# snoozerly.net
KiCad netlist of a schematic drawn in EAGLE
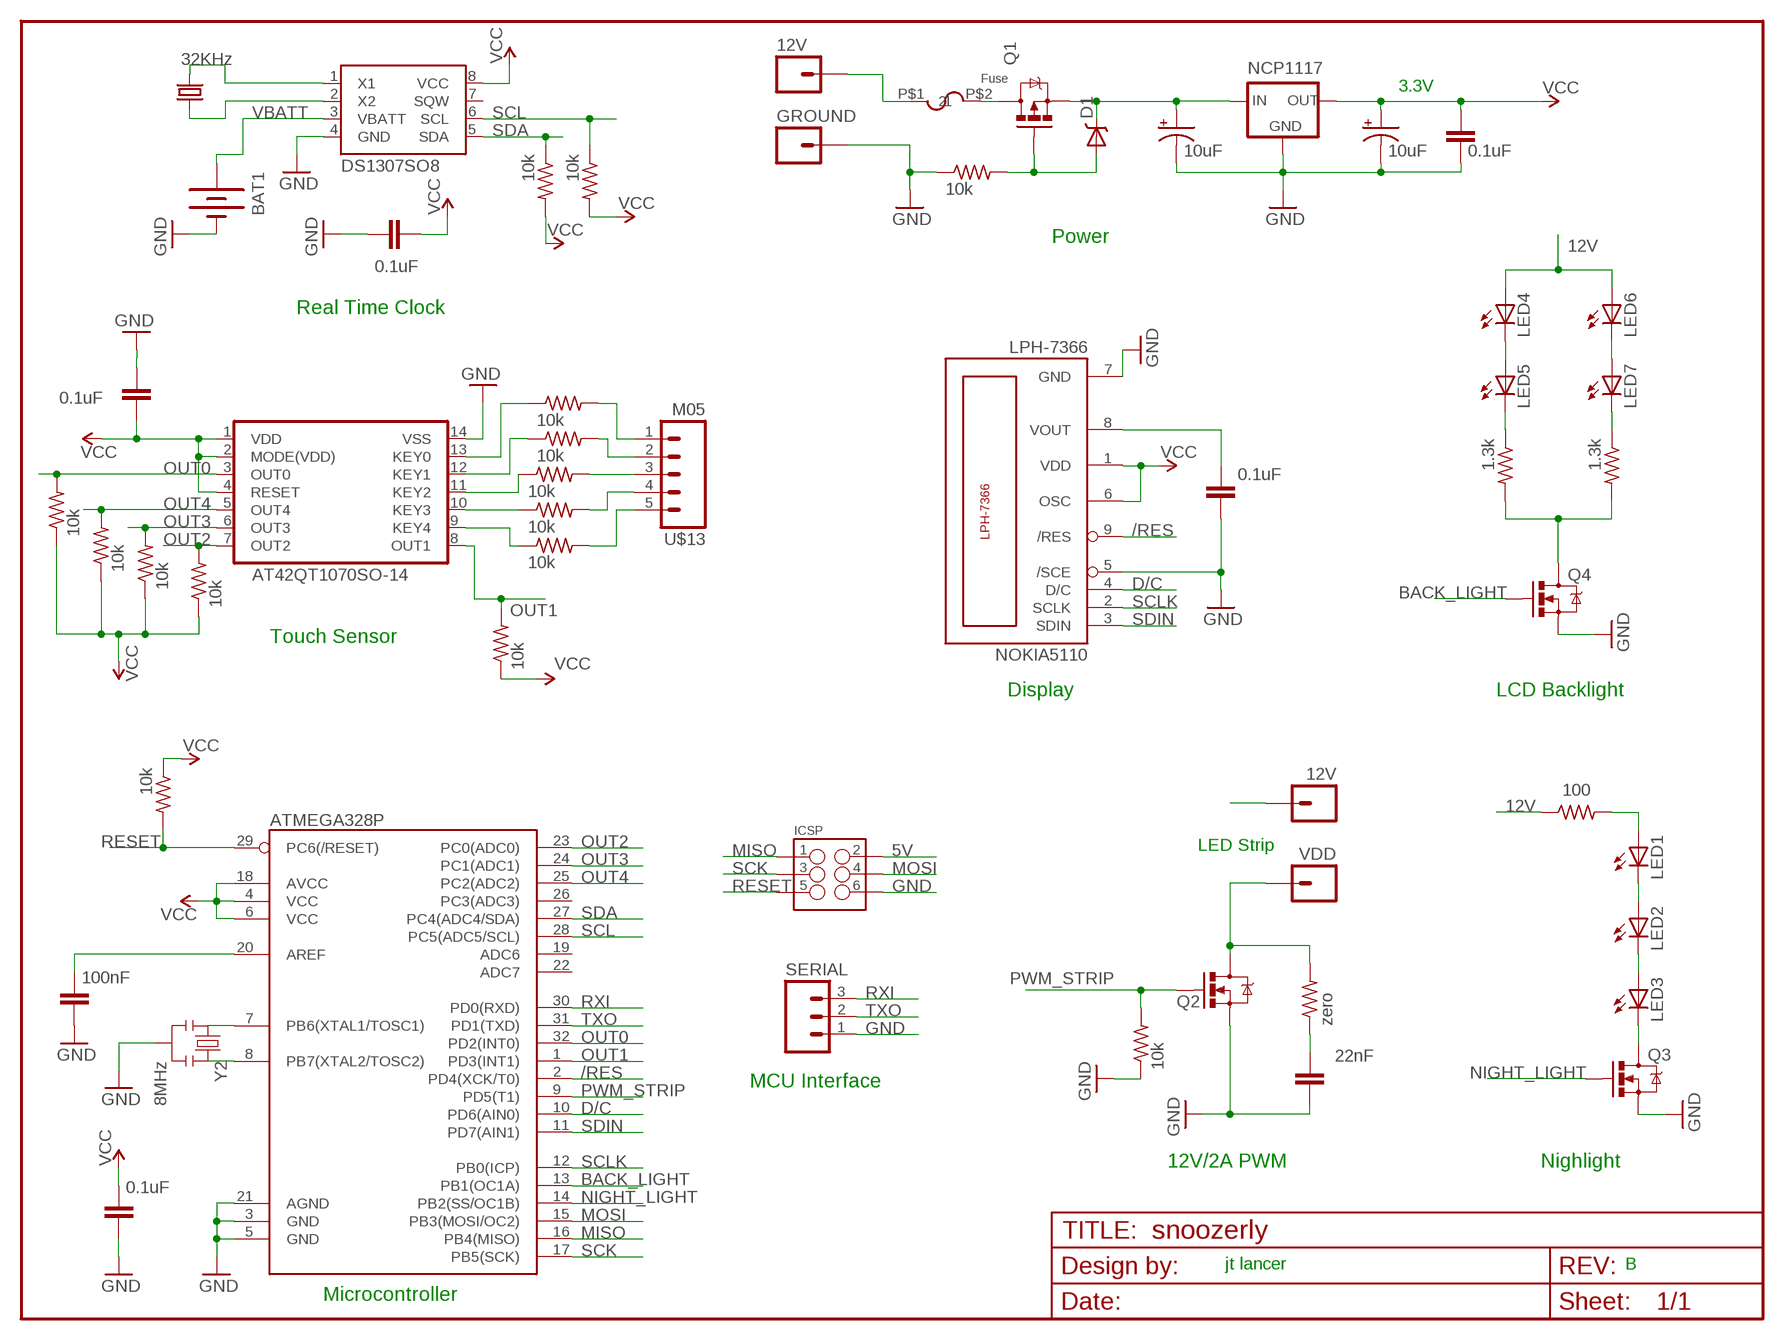
[diagram p0: schematic, sheet 1]

(export (version "E")
  (design (tool "Eeschema 10.0.6"))
  (components
    (comp (ref "12V")
      (value "M01")
      (footprint "eagle-import:M01_BIGHOLE")
      (libsource (lib "eagle-import") (part "M01"))
    )
    (comp (ref "AT42QT1070")
      (value "AT42QT1070SO-14")
      (footprint "eagle-import:SO-14")
      (libsource (lib "eagle-import") (part "AT42QT1070SO-14"))
    )
    (comp (ref "BAT1")
      (value "BATTERY12MM")
      (footprint "eagle-import:BATTCON_12MM")
      (libsource (lib "eagle-import") (part "BATTERY12MM"))
    )
    (comp (ref "C1")
      (value "100nF")
      (footprint "eagle-import:0805")
      (libsource (lib "eagle-import") (part "CAP0805"))
    )
    (comp (ref "C2")
      (value "0.1uF")
      (footprint "eagle-import:0805")
      (libsource (lib "eagle-import") (part "CAP0805"))
    )
    (comp (ref "C3")
      (value "0.1uF")
      (footprint "eagle-import:0805")
      (libsource (lib "eagle-import") (part "CAP0805"))
    )
    (comp (ref "C4")
      (value "22nF")
      (footprint "eagle-import:0805")
      (libsource (lib "eagle-import") (part "CAP0805"))
    )
    (comp (ref "C5")
      (value "10uF")
      (footprint "eagle-import:CAP-PANASONIC-C")
      (libsource (lib "eagle-import") (part "CAP-POLCAP-PANASONIC-C"))
    )
    (comp (ref "C6")
      (value "0.1uF")
      (footprint "eagle-import:0805")
      (libsource (lib "eagle-import") (part "CAP0805"))
    )
    (comp (ref "C7")
      (value "10uF")
      (footprint "eagle-import:CAP-PANASONIC-C")
      (libsource (lib "eagle-import") (part "CAP-POLCAP-PANASONIC-C"))
    )
    (comp (ref "C8")
      (value "0.1uF")
      (footprint "eagle-import:0805")
      (libsource (lib "eagle-import") (part "CAP0805"))
    )
    (comp (ref "C9")
      (value "0.1uF")
      (footprint "eagle-import:0805")
      (libsource (lib "eagle-import") (part "CAP0805"))
    )
    (comp (ref "D1")
      (value "DIODE-SCHOTTKYDO-214AA")
      (footprint "eagle-import:DO-214AA")
      (libsource (lib "eagle-import") (part "DIODE-SCHOTTKYDO-214AA"))
    )
    (comp (ref "GROUND")
      (value "M01")
      (footprint "eagle-import:M01_BIGHOLE")
      (libsource (lib "eagle-import") (part "M01"))
    )
    (comp (ref "ICSP")
      (value "M03X2POGO_PINS")
      (footprint "eagle-import:2X3_POGO")
      (libsource (lib "eagle-import") (part "M03X2POGO_PINS"))
    )
    (comp (ref "LED1")
      (value "LED")
      (footprint "eagle-import:SIDEVIEW-LED")
      (libsource (lib "eagle-import") (part "LED"))
    )
    (comp (ref "LED2")
      (value "LED")
      (footprint "eagle-import:SIDEVIEW-LED")
      (libsource (lib "eagle-import") (part "LED"))
    )
    (comp (ref "LED3")
      (value "LED")
      (footprint "eagle-import:SIDEVIEW-LED")
      (libsource (lib "eagle-import") (part "LED"))
    )
    (comp (ref "LED4")
      (value "LED0603")
      (footprint "eagle-import:LED-0603")
      (libsource (lib "eagle-import") (part "LED0603"))
    )
    (comp (ref "LED5")
      (value "LED0603")
      (footprint "eagle-import:LED-0603")
      (libsource (lib "eagle-import") (part "LED0603"))
    )
    (comp (ref "LED6")
      (value "LED0603")
      (footprint "eagle-import:LED-0603")
      (libsource (lib "eagle-import") (part "LED0603"))
    )
    (comp (ref "LED7")
      (value "LED0603")
      (footprint "eagle-import:LED-0603")
      (libsource (lib "eagle-import") (part "LED0603"))
    )
    (comp (ref "NCP1117")
      (value "VREG-3.3VNCP1117")
      (footprint "eagle-import:TO-252")
      (libsource (lib "eagle-import") (part "VREG-3.3VNCP1117"))
    )
    (comp (ref "NOKIA5110")
      (value "LPH-7366")
      (footprint "eagle-import:NOKIA5110")
      (libsource (lib "eagle-import") (part "LPH-7366"))
    )
    (comp (ref "Q1")
      (value "MOSFET_PCHANNEL")
      (footprint "eagle-import:DPAK")
      (libsource (lib "eagle-import") (part "MOSFET_PCHANNEL"))
    )
    (comp (ref "Q2")
      (value "MOSFET-NCHANNELFDD8780")
      (footprint "eagle-import:DPAK@1")
      (libsource (lib "eagle-import") (part "MOSFET-NCHANNELFDD8780"))
    )
    (comp (ref "Q3")
      (value "MOSFET-NCHANNELBSS123LT1G")
      (footprint "eagle-import:SOT23")
      (libsource (lib "eagle-import") (part "MOSFET-NCHANNELBSS123LT1G"))
    )
    (comp (ref "Q4")
      (value "MOSFET-NCHANNELBSS123LT1G")
      (footprint "eagle-import:SOT23")
      (libsource (lib "eagle-import") (part "MOSFET-NCHANNELBSS123LT1G"))
    )
    (comp (ref "SERIAL")
      (value "M031X03_NO_SILK")
      (footprint "eagle-import:1X03_NO_SILK")
      (libsource (lib "eagle-import") (part "M031X03_NO_SILK"))
    )
    (comp (ref "U$1")
      (value "FRAME_LETTER")
      (footprint "eagle-import:CREATIVE_COMMONS")
      (libsource (lib "eagle-import") (part "FRAME_LETTER"))
    )
    (comp (ref "U$2")
      (value "10k")
      (footprint "eagle-import:RESISTOR-0805")
      (libsource (lib "eagle-import") (part "RESISTOR"))
    )
    (comp (ref "U$3")
      (value "DS1307SO8")
      (footprint "eagle-import:SO08")
      (libsource (lib "eagle-import") (part "DS1307SO8"))
    )
    (comp (ref "U$4")
      (value "10k")
      (footprint "eagle-import:RESISTOR-0805")
      (libsource (lib "eagle-import") (part "RESISTOR"))
    )
    (comp (ref "U$5")
      (value "10k")
      (footprint "eagle-import:RESISTOR-0805")
      (libsource (lib "eagle-import") (part "RESISTOR"))
    )
    (comp (ref "U$6")
      (value "10k")
      (footprint "eagle-import:R0603")
      (libsource (lib "eagle-import") (part "R-US_R0603"))
    )
    (comp (ref "U$7")
      (value "10k")
      (footprint "eagle-import:R0603")
      (libsource (lib "eagle-import") (part "R-US_R0603"))
    )
    (comp (ref "U$8")
      (value "10k")
      (footprint "eagle-import:R0603")
      (libsource (lib "eagle-import") (part "R-US_R0603"))
    )
    (comp (ref "U$9")
      (value "10k")
      (footprint "eagle-import:R0603")
      (libsource (lib "eagle-import") (part "R-US_R0603"))
    )
    (comp (ref "U$10")
      (value "10k")
      (footprint "eagle-import:R0603")
      (libsource (lib "eagle-import") (part "R-US_R0603"))
    )
    (comp (ref "U$11")
      (value "10k")
      (footprint "eagle-import:R0603")
      (libsource (lib "eagle-import") (part "R-US_R0603"))
    )
    (comp (ref "U$12")
      (value "Fuse")
      (footprint "eagle-import:FUSE-LITTLE-251")
      (libsource (lib "eagle-import") (part "FUSE"))
    )
    (comp (ref "U$13")
      (value "M05")
      (footprint "eagle-import:M05-SMD")
      (libsource (lib "eagle-import") (part "M05"))
    )
    (comp (ref "U$14")
      (value "10k")
      (footprint "eagle-import:RESISTOR-0805")
      (libsource (lib "eagle-import") (part "RESISTOR"))
    )
    (comp (ref "U$15")
      (value "10k")
      (footprint "eagle-import:RESISTOR-0805")
      (libsource (lib "eagle-import") (part "RESISTOR"))
    )
    (comp (ref "U$16")
      (value "100")
      (footprint "eagle-import:RESISTOR-0805")
      (libsource (lib "eagle-import") (part "RESISTOR"))
    )
    (comp (ref "U$17")
      (value "1.3k")
      (footprint "eagle-import:RESISTOR-0805")
      (libsource (lib "eagle-import") (part "RESISTOR"))
    )
    (comp (ref "U$18")
      (value "1.3k")
      (footprint "eagle-import:RESISTOR-0805")
      (libsource (lib "eagle-import") (part "RESISTOR"))
    )
    (comp (ref "U$21")
      (value "10k")
      (footprint "eagle-import:R0603")
      (libsource (lib "eagle-import") (part "R-US_R0603"))
    )
    (comp (ref "U$22")
      (value "10k")
      (footprint "eagle-import:R0603")
      (libsource (lib "eagle-import") (part "R-US_R0603"))
    )
    (comp (ref "U$23")
      (value "10k")
      (footprint "eagle-import:R0603")
      (libsource (lib "eagle-import") (part "R-US_R0603"))
    )
    (comp (ref "U$24")
      (value "10k")
      (footprint "eagle-import:R0603")
      (libsource (lib "eagle-import") (part "R-US_R0603"))
    )
    (comp (ref "U$25")
      (value "zero")
      (footprint "eagle-import:R0603")
      (libsource (lib "eagle-import") (part "R-US_R0603"))
    )
    (comp (ref "U$26")
      (value "VDD")
      (footprint "eagle-import:M01_BIGHOLE")
      (libsource (lib "eagle-import") (part "M01"))
    )
    (comp (ref "U$27")
      (value "12V")
      (footprint "eagle-import:M01_BIGHOLE")
      (libsource (lib "eagle-import") (part "M01"))
    )
    (comp (ref "U1")
      (value "ATMEGA328P")
      (footprint "eagle-import:TQFP32-08")
      (libsource (lib "eagle-import") (part "ATMEGA328_SMT"))
    )
    (comp (ref "Y1")
      (value "32KHz")
      (footprint "eagle-import:CRYSTAL-32KHZ-SMD")
      (libsource (lib "eagle-import") (part "CRYSTAL32-SMD"))
    )
    (comp (ref "Y2")
      (value "8MHz")
      (footprint "eagle-import:RESONATOR-SMD")
      (libsource (lib "eagle-import") (part "RESONATOR16MHZ"))
    )
  )
  (nets
    (net (code "1") (name "/12V") (class "Default")
      (node (ref "C5") (pin "+") (pinfunction "+_+") (pintype "passive"))
      (node (ref "D1") (pin "C") (pinfunction "C_C") (pintype "passive"))
      (node (ref "LED4") (pin "A") (pinfunction "A_A") (pintype "passive"))
      (node (ref "LED6") (pin "A") (pinfunction "A_A") (pintype "passive"))
      (node (ref "NCP1117") (pin "3") (pinfunction "IN_3") (pintype "input"))
      (node (ref "Q1") (pin "3") (pinfunction "S_3") (pintype "passive"))
      (node (ref "U$16") (pin "1") (pinfunction "1_1") (pintype "passive"))
      (node (ref "U$27") (pin "1") (pinfunction "1_1") (pintype "passive"))
    )
    (net (code "2") (name "/BACK_LIGHT") (class "Default")
      (node (ref "Q4") (pin "1") (pinfunction "G_1") (pintype "passive"))
      (node (ref "U1") (pin "13") (pinfunction "PB1(OC1A)_13") (pintype "bidirectional"))
    )
    (net (code "3") (name "/D{slash}C") (class "Default")
      (node (ref "NOKIA5110") (pin "4") (pinfunction "D/C_4") (pintype "input"))
      (node (ref "U1") (pin "10") (pinfunction "PD6(AIN0)_10") (pintype "bidirectional"))
    )
    (net (code "4") (name "/MISO") (class "Default")
      (node (ref "ICSP") (pin "P$1") (pinfunction "1_P$1") (pintype "bidirectional"))
      (node (ref "U1") (pin "16") (pinfunction "PB4(MISO)_16") (pintype "bidirectional"))
    )
    (net (code "5") (name "/MOSI") (class "Default")
      (node (ref "ICSP") (pin "P$4") (pinfunction "4_P$4") (pintype "bidirectional"))
      (node (ref "U1") (pin "15") (pinfunction "PB3(MOSI/OC2)_15") (pintype "bidirectional"))
    )
    (net (code "6") (name "/NIGHT_LIGHT") (class "Default")
      (node (ref "Q3") (pin "1") (pinfunction "G_1") (pintype "passive"))
      (node (ref "U1") (pin "14") (pinfunction "PB2(SS/OC1B)_14") (pintype "bidirectional"))
    )
    (net (code "7") (name "/OUT0") (class "Default")
      (node (ref "AT42QT1070") (pin "3") (pinfunction "OUT0_3") (pintype "bidirectional"))
      (node (ref "U$6") (pin "2") (pinfunction "2_2") (pintype "passive"))
      (node (ref "U1") (pin "32") (pinfunction "PD2(INT0)_32") (pintype "bidirectional"))
    )
    (net (code "8") (name "/OUT1") (class "Default")
      (node (ref "AT42QT1070") (pin "8") (pinfunction "OUT1_8") (pintype "bidirectional"))
      (node (ref "U$23") (pin "2") (pinfunction "2_2") (pintype "passive"))
      (node (ref "U1") (pin "1") (pinfunction "PD3(INT1)_1") (pintype "bidirectional"))
    )
    (net (code "9") (name "/OUT2") (class "Default")
      (node (ref "AT42QT1070") (pin "7") (pinfunction "OUT2_7") (pintype "bidirectional"))
      (node (ref "U$22") (pin "2") (pinfunction "2_2") (pintype "passive"))
      (node (ref "U1") (pin "23") (pinfunction "PC0(ADC0)_23") (pintype "bidirectional"))
    )
    (net (code "10") (name "/OUT3") (class "Default")
      (node (ref "AT42QT1070") (pin "6") (pinfunction "OUT3_6") (pintype "bidirectional"))
      (node (ref "U$21") (pin "2") (pinfunction "2_2") (pintype "passive"))
      (node (ref "U1") (pin "24") (pinfunction "PC1(ADC1)_24") (pintype "bidirectional"))
    )
    (net (code "11") (name "/OUT4") (class "Default")
      (node (ref "AT42QT1070") (pin "5") (pinfunction "OUT4_5") (pintype "bidirectional"))
      (node (ref "U$24") (pin "2") (pinfunction "2_2") (pintype "passive"))
      (node (ref "U1") (pin "25") (pinfunction "PC2(ADC2)_25") (pintype "bidirectional"))
    )
    (net (code "12") (name "/PWM_STRIP") (class "Default")
      (node (ref "Q2") (pin "1") (pinfunction "G_1") (pintype "passive"))
      (node (ref "U$15") (pin "2") (pinfunction "2_2") (pintype "passive"))
      (node (ref "U1") (pin "9") (pinfunction "PD5(T1)_9") (pintype "bidirectional"))
    )
    (net (code "13") (name "/RESET") (class "Default")
      (node (ref "ICSP") (pin "P$5") (pinfunction "5_P$5") (pintype "bidirectional"))
      (node (ref "U$2") (pin "2") (pinfunction "2_2") (pintype "passive"))
      (node (ref "U1") (pin "29") (pinfunction "PC6(/RESET)_29") (pintype "bidirectional"))
    )
    (net (code "14") (name "/RXI") (class "Default")
      (node (ref "SERIAL") (pin "3") (pinfunction "3_3") (pintype "passive"))
      (node (ref "U1") (pin "30") (pinfunction "PD0(RXD)_30") (pintype "bidirectional"))
    )
    (net (code "15") (name "/SCK") (class "Default")
      (node (ref "ICSP") (pin "P$3") (pinfunction "3_P$3") (pintype "bidirectional"))
      (node (ref "U1") (pin "17") (pinfunction "PB5(SCK)_17") (pintype "bidirectional"))
    )
    (net (code "16") (name "/SCL") (class "Default")
      (node (ref "U$3") (pin "6") (pinfunction "SCL_6") (pintype "bidirectional"))
      (node (ref "U$5") (pin "1") (pinfunction "1_1") (pintype "passive"))
      (node (ref "U1") (pin "28") (pinfunction "PC5(ADC5/SCL)_28") (pintype "bidirectional"))
    )
    (net (code "17") (name "/SCLK") (class "Default")
      (node (ref "NOKIA5110") (pin "2") (pinfunction "SCLK_2") (pintype "input"))
      (node (ref "U1") (pin "12") (pinfunction "PB0(ICP)_12") (pintype "bidirectional"))
    )
    (net (code "18") (name "/SDA") (class "Default")
      (node (ref "U$3") (pin "5") (pinfunction "SDA_5") (pintype "bidirectional"))
      (node (ref "U$4") (pin "1") (pinfunction "1_1") (pintype "passive"))
      (node (ref "U1") (pin "27") (pinfunction "PC4(ADC4/SDA)_27") (pintype "bidirectional"))
    )
    (net (code "19") (name "/SDIN") (class "Default")
      (node (ref "NOKIA5110") (pin "3") (pinfunction "SDIN_3") (pintype "input"))
      (node (ref "U1") (pin "11") (pinfunction "PD7(AIN1)_11") (pintype "bidirectional"))
    )
    (net (code "20") (name "/TXO") (class "Default")
      (node (ref "SERIAL") (pin "2") (pinfunction "2_2") (pintype "passive"))
      (node (ref "U1") (pin "31") (pinfunction "PD1(TXD)_31") (pintype "bidirectional"))
    )
    (net (code "21") (name "/VBATT") (class "Default")
      (node (ref "BAT1") (pin "PWR@1") (pinfunction "+_PWR@1") (pintype "power_in"))
      (node (ref "U$3") (pin "3") (pinfunction "VBATT_3") (pintype "bidirectional"))
    )
    (net (code "22") (name "/{slash}RES") (class "Default")
      (node (ref "NOKIA5110") (pin "9") (pinfunction "/RES_9") (pintype "input"))
      (node (ref "U1") (pin "2") (pinfunction "PD4(XCK/T0)_2") (pintype "bidirectional"))
    )
    (net (code "23") (name "GND") (class "Default")
      (node (ref "AT42QT1070") (pin "14") (pinfunction "VSS_14") (pintype "power_in"))
      (node (ref "BAT1") (pin "GND") (pinfunction "-_GND") (pintype "power_in"))
      (node (ref "C1") (pin "2") (pinfunction "2_2") (pintype "passive"))
      (node (ref "C2") (pin "2") (pinfunction "2_2") (pintype "passive"))
      (node (ref "C3") (pin "2") (pinfunction "2_2") (pintype "passive"))
      (node (ref "C4") (pin "1") (pinfunction "1_1") (pintype "passive"))
      (node (ref "C5") (pin "-") (pinfunction "-_-") (pintype "passive"))
      (node (ref "C6") (pin "1") (pinfunction "1_1") (pintype "passive"))
      (node (ref "C7") (pin "-") (pinfunction "-_-") (pintype "passive"))
      (node (ref "C8") (pin "2") (pinfunction "2_2") (pintype "passive"))
      (node (ref "C9") (pin "2") (pinfunction "2_2") (pintype "passive"))
      (node (ref "GROUND") (pin "1") (pinfunction "1_1") (pintype "passive"))
      (node (ref "ICSP") (pin "P$6") (pinfunction "6_P$6") (pintype "bidirectional"))
      (node (ref "NCP1117") (pin "1") (pinfunction "GND_1") (pintype "input"))
      (node (ref "NOKIA5110") (pin "5") (pinfunction "/SCE_5") (pintype "input"))
      (node (ref "NOKIA5110") (pin "7") (pinfunction "GND_7") (pintype "power_in"))
      (node (ref "Q2") (pin "3") (pinfunction "S_3") (pintype "passive"))
      (node (ref "Q3") (pin "2") (pinfunction "S_2") (pintype "passive"))
      (node (ref "Q4") (pin "2") (pinfunction "S_2") (pintype "passive"))
      (node (ref "SERIAL") (pin "1") (pinfunction "1_1") (pintype "passive"))
      (node (ref "U$14") (pin "1") (pinfunction "1_1") (pintype "passive"))
      (node (ref "U$15") (pin "1") (pinfunction "1_1") (pintype "passive"))
      (node (ref "U$3") (pin "4") (pinfunction "GND_4") (pintype "bidirectional"))
      (node (ref "U1") (pin "21") (pinfunction "AGND_21") (pintype "bidirectional"))
      (node (ref "U1") (pin "3") (pinfunction "GND_3") (pintype "bidirectional"))
      (node (ref "U1") (pin "5") (pinfunction "GND_5") (pintype "bidirectional"))
      (node (ref "Y2") (pin "2") (pinfunction "2_2") (pintype "passive"))
    )
    (net (code "24") (name "Net-(AT42QT1070-KEY0)") (class "Default")
      (node (ref "AT42QT1070") (pin "13") (pinfunction "KEY0_13") (pintype "bidirectional"))
      (node (ref "U$7") (pin "1") (pinfunction "1_1") (pintype "passive"))
    )
    (net (code "25") (name "Net-(AT42QT1070-KEY1)") (class "Default")
      (node (ref "AT42QT1070") (pin "12") (pinfunction "KEY1_12") (pintype "bidirectional"))
      (node (ref "U$8") (pin "1") (pinfunction "1_1") (pintype "passive"))
    )
    (net (code "26") (name "Net-(AT42QT1070-KEY2)") (class "Default")
      (node (ref "AT42QT1070") (pin "11") (pinfunction "KEY2_11") (pintype "bidirectional"))
      (node (ref "U$9") (pin "1") (pinfunction "1_1") (pintype "passive"))
    )
    (net (code "27") (name "Net-(AT42QT1070-KEY3)") (class "Default")
      (node (ref "AT42QT1070") (pin "10") (pinfunction "KEY3_10") (pintype "bidirectional"))
      (node (ref "U$10") (pin "1") (pinfunction "1_1") (pintype "passive"))
    )
    (net (code "28") (name "Net-(AT42QT1070-KEY4)") (class "Default")
      (node (ref "AT42QT1070") (pin "9") (pinfunction "KEY4_9") (pintype "bidirectional"))
      (node (ref "U$11") (pin "1") (pinfunction "1_1") (pintype "passive"))
    )
    (net (code "29") (name "Net-(C4-Pad2)") (class "Default")
      (node (ref "C4") (pin "2") (pinfunction "2_2") (pintype "passive"))
      (node (ref "U$25") (pin "1") (pinfunction "1_1") (pintype "passive"))
    )
    (net (code "30") (name "Net-(LED1-A)") (class "Default")
      (node (ref "LED1") (pin "P$1") (pinfunction "A_P$1") (pintype "passive"))
      (node (ref "U$16") (pin "2") (pinfunction "2_2") (pintype "passive"))
    )
    (net (code "31") (name "Net-(LED1-C)") (class "Default")
      (node (ref "LED1") (pin "P$2") (pinfunction "C_P$2") (pintype "passive"))
      (node (ref "LED2") (pin "P$1") (pinfunction "A_P$1") (pintype "passive"))
    )
    (net (code "32") (name "Net-(LED2-C)") (class "Default")
      (node (ref "LED2") (pin "P$2") (pinfunction "C_P$2") (pintype "passive"))
      (node (ref "LED3") (pin "P$1") (pinfunction "A_P$1") (pintype "passive"))
    )
    (net (code "33") (name "Net-(LED3-C)") (class "Default")
      (node (ref "LED3") (pin "P$2") (pinfunction "C_P$2") (pintype "passive"))
      (node (ref "Q3") (pin "3") (pinfunction "D_3") (pintype "passive"))
    )
    (net (code "34") (name "Net-(LED4-PadC)") (class "Default")
      (node (ref "LED4") (pin "C") (pinfunction "C_C") (pintype "passive"))
      (node (ref "LED5") (pin "A") (pinfunction "A_A") (pintype "passive"))
    )
    (net (code "35") (name "Net-(LED5-PadC)") (class "Default")
      (node (ref "LED5") (pin "C") (pinfunction "C_C") (pintype "passive"))
      (node (ref "U$17") (pin "1") (pinfunction "1_1") (pintype "passive"))
    )
    (net (code "36") (name "Net-(LED6-PadC)") (class "Default")
      (node (ref "LED6") (pin "C") (pinfunction "C_C") (pintype "passive"))
      (node (ref "LED7") (pin "A") (pinfunction "A_A") (pintype "passive"))
    )
    (net (code "37") (name "Net-(LED7-PadC)") (class "Default")
      (node (ref "LED7") (pin "C") (pinfunction "C_C") (pintype "passive"))
      (node (ref "U$18") (pin "1") (pinfunction "1_1") (pintype "passive"))
    )
    (net (code "38") (name "Net-(NOKIA5110-VOUT)") (class "Default")
      (node (ref "C6") (pin "2") (pinfunction "2_2") (pintype "passive"))
      (node (ref "NOKIA5110") (pin "8") (pinfunction "VOUT_8") (pintype "passive"))
    )
    (net (code "39") (name "Net-(Q1-D)") (class "Default")
      (node (ref "Q1") (pin "4") (pinfunction "D_4") (pintype "passive"))
      (node (ref "U$12") (pin "P$2") (pinfunction "2_P$2") (pintype "bidirectional"))
    )
    (net (code "40") (name "Net-(Q1-G)") (class "Default")
      (node (ref "D1") (pin "A") (pinfunction "A_A") (pintype "passive"))
      (node (ref "Q1") (pin "1") (pinfunction "G_1") (pintype "passive"))
      (node (ref "U$14") (pin "2") (pinfunction "2_2") (pintype "passive"))
    )
    (net (code "41") (name "Net-(Q2-D)") (class "Default")
      (node (ref "Q2") (pin "4") (pinfunction "D_4") (pintype "passive"))
      (node (ref "U$25") (pin "2") (pinfunction "2_2") (pintype "passive"))
      (node (ref "U$26") (pin "1") (pinfunction "1_1") (pintype "passive"))
    )
    (net (code "42") (name "Net-(Q4-D)") (class "Default")
      (node (ref "Q4") (pin "3") (pinfunction "D_3") (pintype "passive"))
      (node (ref "U$17") (pin "2") (pinfunction "2_2") (pintype "passive"))
      (node (ref "U$18") (pin "2") (pinfunction "2_2") (pintype "passive"))
    )
    (net (code "43") (name "Net-(U$3-X1)") (class "Default")
      (node (ref "U$3") (pin "1") (pinfunction "X1_1") (pintype "bidirectional"))
      (node (ref "Y1") (pin "X2") (pinfunction "2_X2") (pintype "passive"))
    )
    (net (code "44") (name "Net-(U$3-X2)") (class "Default")
      (node (ref "U$3") (pin "2") (pinfunction "X2_2") (pintype "bidirectional"))
      (node (ref "Y1") (pin "X1") (pinfunction "1_X1") (pintype "passive"))
    )
    (net (code "45") (name "Net-(U$10-Pad2)") (class "Default")
      (node (ref "U$10") (pin "2") (pinfunction "2_2") (pintype "passive"))
      (node (ref "U$13") (pin "4") (pinfunction "4_4") (pintype "passive"))
    )
    (net (code "46") (name "Net-(U$11-Pad2)") (class "Default")
      (node (ref "U$11") (pin "2") (pinfunction "2_2") (pintype "passive"))
      (node (ref "U$13") (pin "5") (pinfunction "5_5") (pintype "passive"))
    )
    (net (code "47") (name "Net-(U$12-1)") (class "Default")
      (node (ref "12V") (pin "1") (pinfunction "1_1") (pintype "passive"))
      (node (ref "U$12") (pin "P$1") (pinfunction "1_P$1") (pintype "bidirectional"))
    )
    (net (code "48") (name "Net-(U$13-Pad1)") (class "Default")
      (node (ref "U$13") (pin "1") (pinfunction "1_1") (pintype "passive"))
      (node (ref "U$7") (pin "2") (pinfunction "2_2") (pintype "passive"))
    )
    (net (code "49") (name "Net-(U$13-Pad2)") (class "Default")
      (node (ref "U$13") (pin "2") (pinfunction "2_2") (pintype "passive"))
      (node (ref "U$8") (pin "2") (pinfunction "2_2") (pintype "passive"))
    )
    (net (code "50") (name "Net-(U$13-Pad3)") (class "Default")
      (node (ref "U$13") (pin "3") (pinfunction "3_3") (pintype "passive"))
      (node (ref "U$9") (pin "2") (pinfunction "2_2") (pintype "passive"))
    )
    (net (code "51") (name "Net-(U1-AREF)") (class "Default")
      (node (ref "C1") (pin "1") (pinfunction "1_1") (pintype "passive"))
      (node (ref "U1") (pin "20") (pinfunction "AREF_20") (pintype "bidirectional"))
    )
    (net (code "52") (name "Net-(U1-PB6(XTAL1{slash}TOSC1))") (class "Default")
      (node (ref "U1") (pin "7") (pinfunction "PB6(XTAL1/TOSC1)_7") (pintype "bidirectional"))
      (node (ref "Y2") (pin "1") (pinfunction "1_1") (pintype "passive"))
    )
    (net (code "53") (name "Net-(U1-PB7(XTAL2{slash}TOSC2))") (class "Default")
      (node (ref "U1") (pin "8") (pinfunction "PB7(XTAL2/TOSC2)_8") (pintype "bidirectional"))
      (node (ref "Y2") (pin "3") (pinfunction "3_3") (pintype "passive"))
    )
    (net (code "54") (name "VCC") (class "Default")
      (node (ref "AT42QT1070") (pin "1") (pinfunction "VDD_1") (pintype "power_in"))
      (node (ref "AT42QT1070") (pin "2") (pinfunction "MODE(VDD)_2") (pintype "bidirectional"))
      (node (ref "AT42QT1070") (pin "4") (pinfunction "RESET_4") (pintype "bidirectional"))
      (node (ref "C2") (pin "1") (pinfunction "1_1") (pintype "passive"))
      (node (ref "C3") (pin "1") (pinfunction "1_1") (pintype "passive"))
      (node (ref "C7") (pin "+") (pinfunction "+_+") (pintype "passive"))
      (node (ref "C8") (pin "1") (pinfunction "1_1") (pintype "passive"))
      (node (ref "C9") (pin "1") (pinfunction "1_1") (pintype "passive"))
      (node (ref "ICSP") (pin "P$2") (pinfunction "2_P$2") (pintype "bidirectional"))
      (node (ref "NCP1117") (pin "2") (pinfunction "OUT_2") (pintype "passive"))
      (node (ref "NOKIA5110") (pin "1") (pinfunction "VDD_1") (pintype "power_in"))
      (node (ref "NOKIA5110") (pin "6") (pinfunction "OSC_6") (pintype "passive"))
      (node (ref "U$2") (pin "1") (pinfunction "1_1") (pintype "passive"))
      (node (ref "U$21") (pin "1") (pinfunction "1_1") (pintype "passive"))
      (node (ref "U$22") (pin "1") (pinfunction "1_1") (pintype "passive"))
      (node (ref "U$23") (pin "1") (pinfunction "1_1") (pintype "passive"))
      (node (ref "U$24") (pin "1") (pinfunction "1_1") (pintype "passive"))
      (node (ref "U$3") (pin "8") (pinfunction "VCC_8") (pintype "bidirectional"))
      (node (ref "U$4") (pin "2") (pinfunction "2_2") (pintype "passive"))
      (node (ref "U$5") (pin "2") (pinfunction "2_2") (pintype "passive"))
      (node (ref "U$6") (pin "1") (pinfunction "1_1") (pintype "passive"))
      (node (ref "U1") (pin "18") (pinfunction "AVCC_18") (pintype "bidirectional"))
      (node (ref "U1") (pin "4") (pinfunction "VCC_4") (pintype "bidirectional"))
      (node (ref "U1") (pin "6") (pinfunction "VCC_6") (pintype "bidirectional"))
    )
    (net (code "55") (name "unconnected-(U$3-SQW-Pad7)") (class "Default")
      (node (ref "U$3") (pin "7") (pinfunction "SQW_7") (pintype "bidirectional"))
    )
    (net (code "56") (name "unconnected-(U1-ADC6-Pad19)") (class "Default")
      (node (ref "U1") (pin "19") (pinfunction "ADC6_19") (pintype "bidirectional"))
    )
    (net (code "57") (name "unconnected-(U1-ADC7-Pad22)") (class "Default")
      (node (ref "U1") (pin "22") (pinfunction "ADC7_22") (pintype "bidirectional"))
    )
    (net (code "58") (name "unconnected-(U1-PC3(ADC3)-Pad26)") (class "Default")
      (node (ref "U1") (pin "26") (pinfunction "PC3(ADC3)_26") (pintype "bidirectional"))
    )
  )
)
